# DesignVFD-Ring.net
KiCad netlist of a schematic drawn in EAGLE
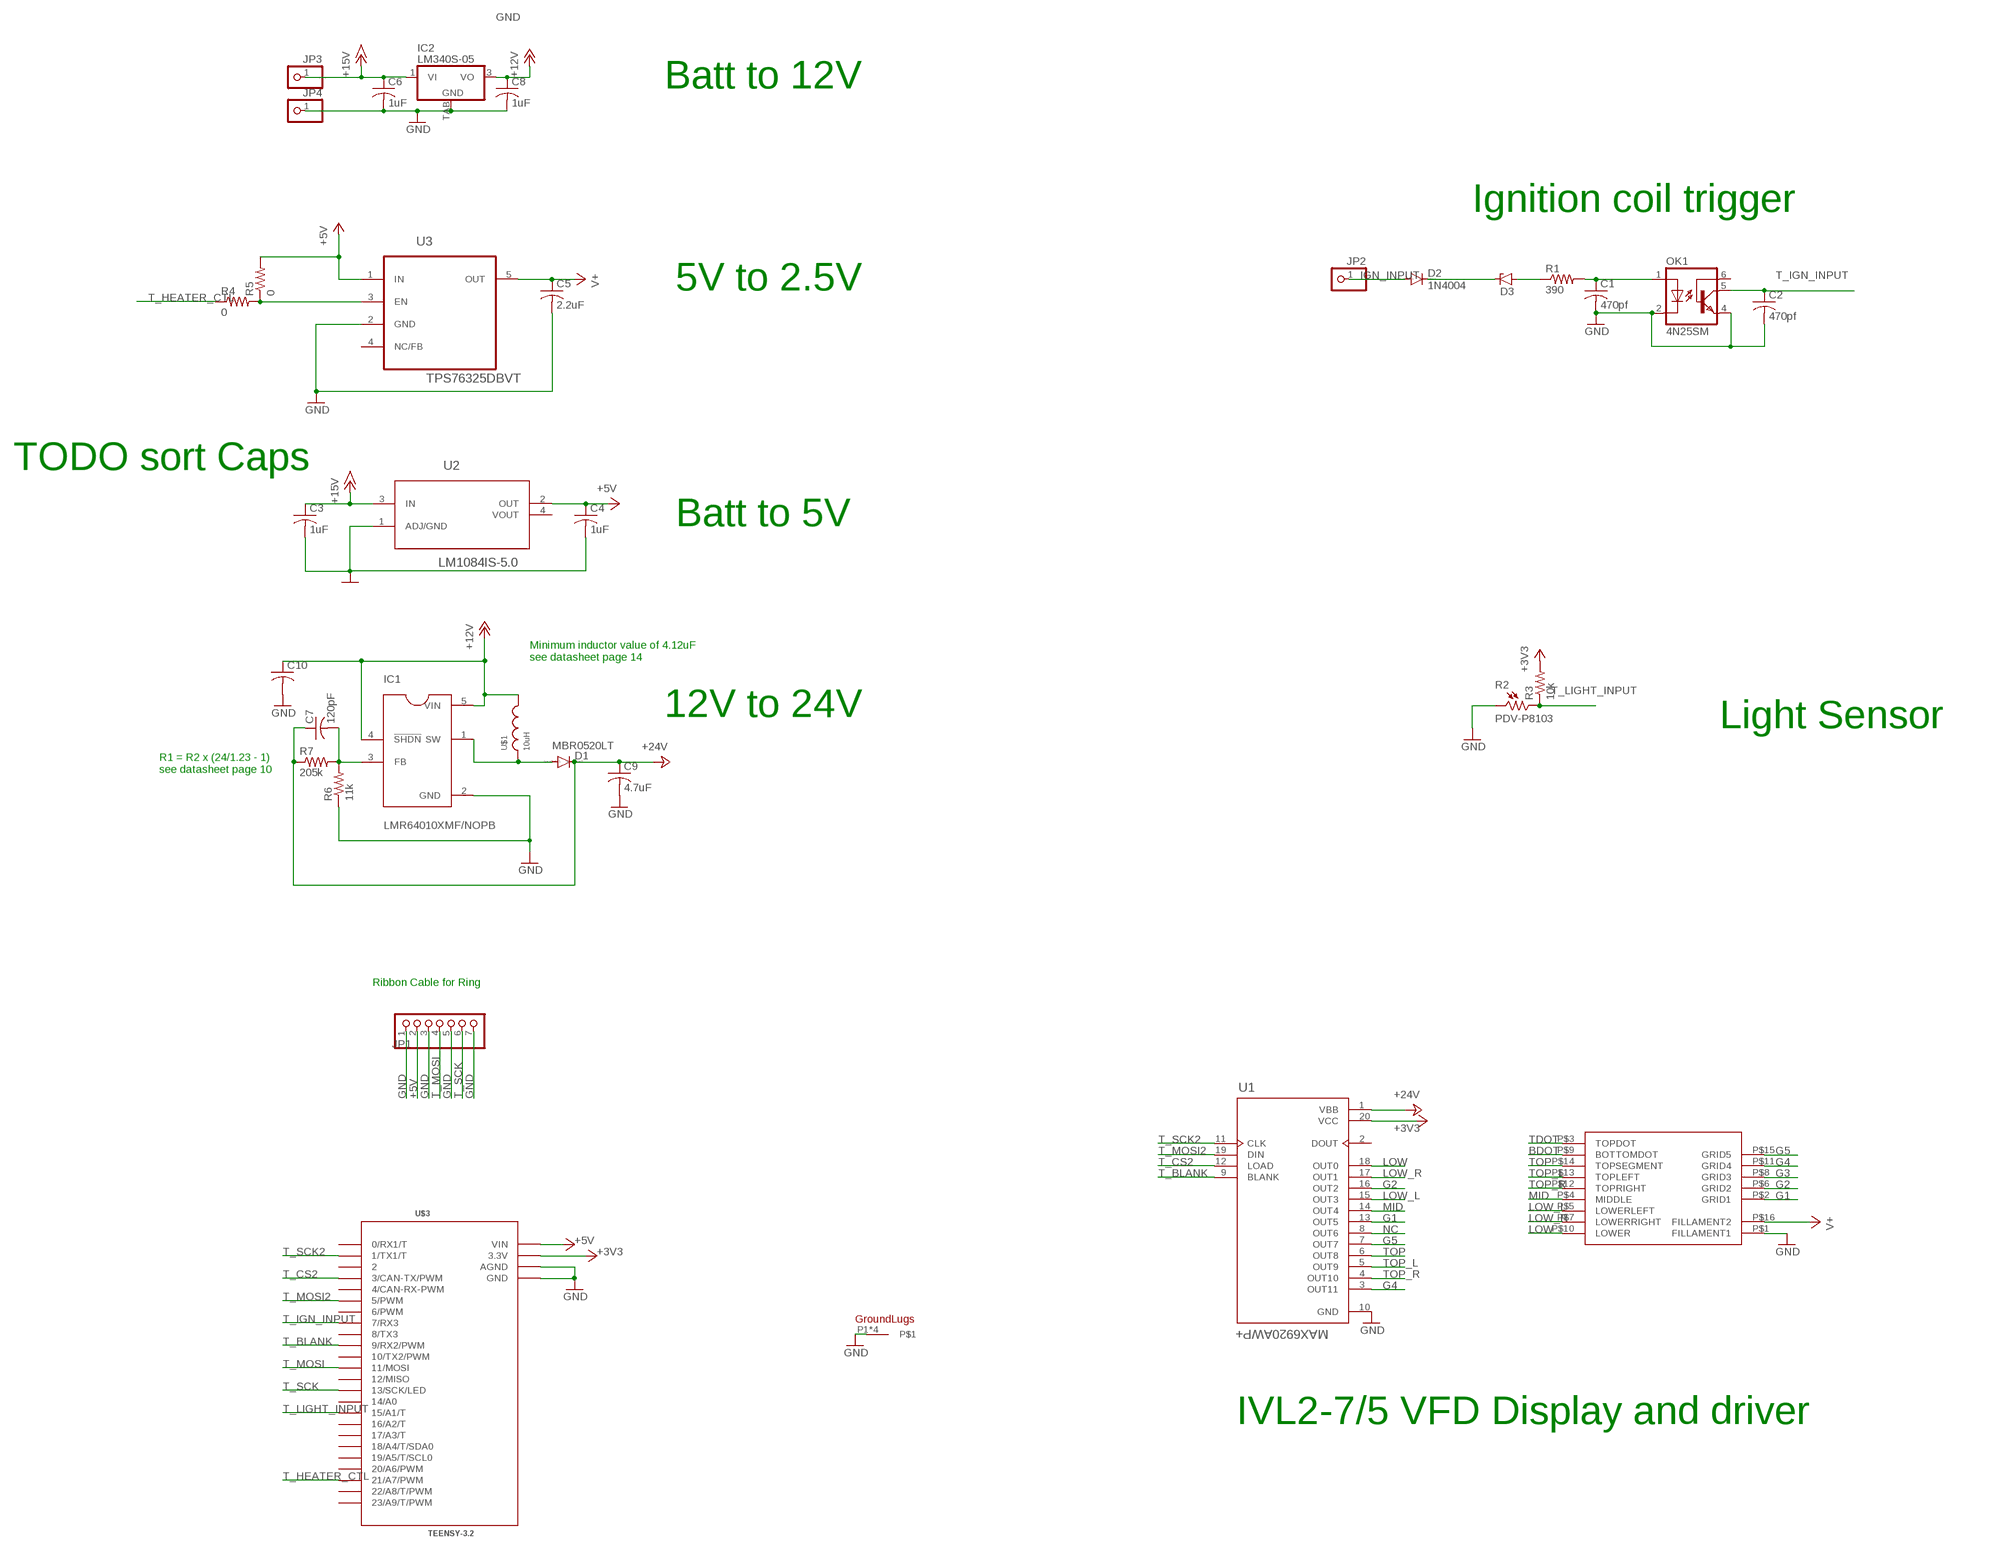
[diagram p0: schematic, sheet 1]

(export (version "E")
  (design (tool "Eeschema 10.0.6"))
  (components
    (comp (ref "C1")
      (value "470pf")
      (footprint "eagle-import:C0805")
      (libsource (lib "eagle-import") (part "C-USC0805"))
    )
    (comp (ref "C2")
      (value "470pf")
      (footprint "eagle-import:C0805")
      (libsource (lib "eagle-import") (part "C-USC0805"))
    )
    (comp (ref "C3")
      (value "1uF")
      (footprint "eagle-import:C0805")
      (libsource (lib "eagle-import") (part "C-USC0805"))
    )
    (comp (ref "C4")
      (value "1uF")
      (footprint "eagle-import:C0805")
      (libsource (lib "eagle-import") (part "C-USC0805"))
    )
    (comp (ref "C5")
      (value "2.2uF")
      (footprint "eagle-import:C0805")
      (libsource (lib "eagle-import") (part "C-USC0805"))
    )
    (comp (ref "C6")
      (value "1uF")
      (footprint "eagle-import:C0805")
      (libsource (lib "eagle-import") (part "C-USC0805"))
    )
    (comp (ref "C7")
      (value "120pF")
      (footprint "eagle-import:C0805")
      (libsource (lib "eagle-import") (part "C-USC0805"))
    )
    (comp (ref "C8")
      (value "1uF")
      (footprint "eagle-import:C0805")
      (libsource (lib "eagle-import") (part "C-USC0805"))
    )
    (comp (ref "C9")
      (value "4.7uF")
      (footprint "eagle-import:C0805")
      (libsource (lib "eagle-import") (part "C-USC0805"))
    )
    (comp (ref "C10")
      (value "C-US025-050X050")
      (footprint "eagle-import:C025-050X050")
      (libsource (lib "eagle-import") (part "C-US025-050X050"))
    )
    (comp (ref "D1")
      (value "MBR0520LT")
      (footprint "eagle-import:SOD123")
      (libsource (lib "eagle-import") (part "MBR0520LT"))
    )
    (comp (ref "D2")
      (value "1N4004")
      (footprint "eagle-import:DO41-10")
      (libsource (lib "eagle-import") (part "1N4004"))
    )
    (comp (ref "D3")
      (value "ZENER-DIODEDO41Z10")
      (footprint "eagle-import:DO41Z10")
      (libsource (lib "eagle-import") (part "ZENER-DIODEDO41Z10"))
    )
    (comp (ref "IC1")
      (value "LMR64010XMF/NOPB")
      (footprint "eagle-import:SOT95P280X145-5N")
      (fields (field (name "DIGI-KEY_PART_NUMBER") "296-38770-1-ND") (field (name "MF") "Texas Instruments"))
      (libsource (lib "eagle-import") (part "LMR64010XMF/NOPB"))
    )
    (comp (ref "IC2")
      (value "LM340S-05")
      (footprint "eagle-import:TO263-3")
      (libsource (lib "eagle-import") (part "LM340?-S05"))
    )
    (comp (ref "JP1")
      (value "PINHD-1X7")
      (footprint "eagle-import:1X07")
      (libsource (lib "eagle-import") (part "PINHD-1X7"))
    )
    (comp (ref "JP2")
      (value "PINHD-1X1")
      (footprint "eagle-import:1X01")
      (libsource (lib "eagle-import") (part "PINHD-1X1"))
    )
    (comp (ref "JP3")
      (value "PINHD-1X1")
      (footprint "eagle-import:1X01")
      (libsource (lib "eagle-import") (part "PINHD-1X1"))
    )
    (comp (ref "JP4")
      (value "PINHD-1X1")
      (footprint "eagle-import:1X01")
      (libsource (lib "eagle-import") (part "PINHD-1X1"))
    )
    (comp (ref "OK1")
      (value "4N25SM")
      (footprint "eagle-import:DIL6-SMD")
      (fields (field (name "MF") "ON Semiconductor"))
      (libsource (lib "eagle-import") (part "4N25SM"))
    )
    (comp (ref "R1")
      (value "390")
      (footprint "eagle-import:R0805")
      (libsource (lib "eagle-import") (part "R-US_R0805"))
    )
    (comp (ref "R2")
      (value "PDV-P8103")
      (footprint "eagle-import:PHODET_PDV-P8103")
      (fields (field (name "MF") "Advanced Photonix"))
      (libsource (lib "eagle-import") (part "PDV-P8103"))
    )
    (comp (ref "R3")
      (value "10k")
      (footprint "eagle-import:R0805")
      (libsource (lib "eagle-import") (part "R-US_R0805"))
    )
    (comp (ref "R4")
      (value "0")
      (footprint "eagle-import:R0805")
      (libsource (lib "eagle-import") (part "R-US_R0805"))
    )
    (comp (ref "R5")
      (value "0")
      (footprint "eagle-import:R0805")
      (libsource (lib "eagle-import") (part "R-US_R0805"))
    )
    (comp (ref "R6")
      (value "11k")
      (footprint "eagle-import:R0805")
      (libsource (lib "eagle-import") (part "R-US_R0805"))
    )
    (comp (ref "R7")
      (value "205k")
      (footprint "eagle-import:R0805")
      (libsource (lib "eagle-import") (part "R-US_R0805"))
    )
    (comp (ref "U$1")
      (value "10uH")
      (footprint "eagle-import:732-1416-ND")
      (libsource (lib "eagle-import") (part "732-1416-ND732-1416-ND"))
    )
    (comp (ref "U$2")
      (value "IVL2-7/5")
      (footprint "eagle-import:IVL2-7_5")
      (libsource (lib "eagle-import") (part "IVL2-7/5"))
    )
    (comp (ref "U$3")
      (value "TEENSY-3.2")
      (footprint "eagle-import:TEENSY3.2")
      (libsource (lib "eagle-import") (part "TEENSY-3.2"))
    )
    (comp (ref "U$4")
      (value "LUMINI3")
      (footprint "eagle-import:STANDOFF-ELECTRICAL")
      (libsource (lib "eagle-import") (part "LUMINI3"))
    )
    (comp (ref "U1")
      (value "MAX6920AWP+")
      (footprint "eagle-import:SOIC127P1032X265-20N")
      (fields (field (name "DIGI-KEY_PART_NUMBER") "MAX6920AWP+-ND") (field (name "MF") "Maxim Integrated"))
      (libsource (lib "eagle-import") (part "MAX6920AWP+"))
    )
    (comp (ref "U2")
      (value "LM1084IS-5.0")
      (footprint "eagle-import:TO254P1435X457-3N")
      (fields (field (name "MF") "Texas Instruments") (field (name "MP") "LM1084IS50"))
      (libsource (lib "eagle-import") (part "LM1084IS-5.0"))
    )
    (comp (ref "U3")
      (value "TPS76325DBVT")
      (footprint "eagle-import:SOT95P280X145-5N")
      (fields (field (name "DIGI-KEY_PART_NUMBER") "296-2701-1-ND") (field (name "MF") "Texas Instruments"))
      (libsource (lib "eagle-import") (part "TPS76325DBVT"))
    )
  )
  (nets
    (net (code "1") (name "+3V3") (class "Default")
      (node (ref "R3") (pin "2") (pinfunction "2_2") (pintype "passive"))
      (node (ref "U$3") (pin "3V3+") (pinfunction "3.3V_3V3+") (pintype "power_in"))
      (node (ref "U1") (pin "20") (pinfunction "VCC_20") (pintype "power_in"))
    )
    (net (code "2") (name "+5V") (class "Default")
      (node (ref "C4") (pin "1") (pinfunction "1_1") (pintype "passive"))
      (node (ref "JP1") (pin "2") (pinfunction "2_2") (pintype "passive"))
      (node (ref "R5") (pin "2") (pinfunction "2_2") (pintype "passive"))
      (node (ref "U$3") (pin "VIN") (pinfunction "VIN_VIN") (pintype "power_in"))
      (node (ref "U2") (pin "2") (pinfunction "OUT_2") (pintype "output"))
      (node (ref "U3") (pin "1") (pinfunction "IN_1") (pintype "power_in"))
    )
    (net (code "3") (name "+12V") (class "Default")
      (node (ref "C10") (pin "1") (pinfunction "1_1") (pintype "passive"))
      (node (ref "C8") (pin "1") (pinfunction "1_1") (pintype "passive"))
      (node (ref "IC1") (pin "4") (pinfunction "~{SHDN}_4") (pintype "input"))
      (node (ref "IC1") (pin "5") (pinfunction "VIN_5") (pintype "power_in"))
      (node (ref "IC2") (pin "3") (pinfunction "VO_3") (pintype "passive"))
      (node (ref "U$1") (pin "P$2") (pinfunction "P$2_P$2") (pintype "bidirectional"))
    )
    (net (code "4") (name "+15V") (class "Default")
      (node (ref "C3") (pin "1") (pinfunction "1_1") (pintype "passive"))
      (node (ref "C6") (pin "1") (pinfunction "1_1") (pintype "passive"))
      (node (ref "IC2") (pin "1") (pinfunction "VI_1") (pintype "input"))
      (node (ref "JP3") (pin "1") (pinfunction "1_1") (pintype "passive"))
      (node (ref "U2") (pin "3") (pinfunction "IN_3") (pintype "power_in"))
    )
    (net (code "5") (name "+24V") (class "Default")
      (node (ref "C7") (pin "1") (pinfunction "1_1") (pintype "passive"))
      (node (ref "C9") (pin "1") (pinfunction "1_1") (pintype "passive"))
      (node (ref "D1") (pin "C") (pinfunction "C_C") (pintype "passive"))
      (node (ref "R7") (pin "1") (pinfunction "1_1") (pintype "passive"))
      (node (ref "U1") (pin "1") (pinfunction "VBB_1") (pintype "power_in"))
    )
    (net (code "6") (name "/BDOT") (class "Default")
      (node (ref "U$2") (pin "P$9") (pinfunction "BOTTOMDOT_P$9") (pintype "bidirectional"))
    )
    (net (code "7") (name "/G1") (class "Default")
      (node (ref "U$2") (pin "P$2") (pinfunction "GRID1_P$2") (pintype "bidirectional"))
      (node (ref "U1") (pin "13") (pinfunction "OUT5_13") (pintype "output"))
    )
    (net (code "8") (name "/G2") (class "Default")
      (node (ref "U$2") (pin "P$6") (pinfunction "GRID2_P$6") (pintype "bidirectional"))
      (node (ref "U1") (pin "16") (pinfunction "OUT2_16") (pintype "output"))
    )
    (net (code "9") (name "/G3") (class "Default")
      (node (ref "U$2") (pin "P$8") (pinfunction "GRID3_P$8") (pintype "bidirectional"))
    )
    (net (code "10") (name "/G4") (class "Default")
      (node (ref "U$2") (pin "P$11") (pinfunction "GRID4_P$11") (pintype "bidirectional"))
      (node (ref "U1") (pin "3") (pinfunction "OUT11_3") (pintype "output"))
    )
    (net (code "11") (name "/G5") (class "Default")
      (node (ref "U$2") (pin "P$15") (pinfunction "GRID5_P$15") (pintype "bidirectional"))
      (node (ref "U1") (pin "7") (pinfunction "OUT7_7") (pintype "output"))
    )
    (net (code "12") (name "/IGN_INPUT") (class "Default")
      (node (ref "D2") (pin "A") (pinfunction "A_A") (pintype "passive"))
      (node (ref "JP2") (pin "1") (pinfunction "1_1") (pintype "passive"))
    )
    (net (code "13") (name "/LOW") (class "Default")
      (node (ref "U$2") (pin "P$10") (pinfunction "LOWER_P$10") (pintype "bidirectional"))
      (node (ref "U1") (pin "18") (pinfunction "OUT0_18") (pintype "output"))
    )
    (net (code "14") (name "/LOW_L") (class "Default")
      (node (ref "U$2") (pin "P$5") (pinfunction "LOWERLEFT_P$5") (pintype "bidirectional"))
      (node (ref "U1") (pin "15") (pinfunction "OUT3_15") (pintype "output"))
    )
    (net (code "15") (name "/LOW_R") (class "Default")
      (node (ref "U$2") (pin "P$7") (pinfunction "LOWERRIGHT_P$7") (pintype "bidirectional"))
      (node (ref "U1") (pin "17") (pinfunction "OUT1_17") (pintype "output"))
    )
    (net (code "16") (name "/MID") (class "Default")
      (node (ref "U$2") (pin "P$4") (pinfunction "MIDDLE_P$4") (pintype "bidirectional"))
      (node (ref "U1") (pin "14") (pinfunction "OUT4_14") (pintype "output"))
    )
    (net (code "17") (name "/NC") (class "Default")
      (node (ref "U1") (pin "8") (pinfunction "OUT6_8") (pintype "output"))
    )
    (net (code "18") (name "/TDOT") (class "Default")
      (node (ref "U$2") (pin "P$3") (pinfunction "TOPDOT_P$3") (pintype "bidirectional"))
    )
    (net (code "19") (name "/TOP") (class "Default")
      (node (ref "U$2") (pin "P$14") (pinfunction "TOPSEGMENT_P$14") (pintype "bidirectional"))
      (node (ref "U1") (pin "6") (pinfunction "OUT8_6") (pintype "output"))
    )
    (net (code "20") (name "/TOP_L") (class "Default")
      (node (ref "U$2") (pin "P$13") (pinfunction "TOPLEFT_P$13") (pintype "bidirectional"))
      (node (ref "U1") (pin "5") (pinfunction "OUT9_5") (pintype "output"))
    )
    (net (code "21") (name "/TOP_R") (class "Default")
      (node (ref "U$2") (pin "P$12") (pinfunction "TOPRIGHT_P$12") (pintype "bidirectional"))
      (node (ref "U1") (pin "4") (pinfunction "OUT10_4") (pintype "output"))
    )
    (net (code "22") (name "/T_BLANK") (class "Default")
      (node (ref "U$3") (pin "9") (pinfunction "9/RX2/PWM_9") (pintype "bidirectional"))
      (node (ref "U1") (pin "9") (pinfunction "BLANK_9") (pintype "input"))
    )
    (net (code "23") (name "/T_CS2") (class "Default")
      (node (ref "U$3") (pin "3") (pinfunction "3/CAN-TX/PWM_3") (pintype "bidirectional"))
      (node (ref "U1") (pin "12") (pinfunction "LOAD_12") (pintype "input"))
    )
    (net (code "24") (name "/T_HEATER_CTL") (class "Default")
      (node (ref "R4") (pin "1") (pinfunction "1_1") (pintype "passive"))
      (node (ref "U$3") (pin "21") (pinfunction "21/A7/PWM_21") (pintype "bidirectional"))
    )
    (net (code "25") (name "/T_IGN_INPUT") (class "Default")
      (node (ref "C2") (pin "1") (pinfunction "1_1") (pintype "passive"))
      (node (ref "OK1") (pin "5") (pinfunction "COL_5") (pintype "passive"))
      (node (ref "U$3") (pin "7") (pinfunction "7/RX3_7") (pintype "bidirectional"))
    )
    (net (code "26") (name "/T_LIGHT_INPUT") (class "Default")
      (node (ref "R2") (pin "2") (pinfunction "2_2") (pintype "passive"))
      (node (ref "R3") (pin "1") (pinfunction "1_1") (pintype "passive"))
      (node (ref "U$3") (pin "15") (pinfunction "15/A1/T_15") (pintype "bidirectional"))
    )
    (net (code "27") (name "/T_MOSI") (class "Default")
      (node (ref "JP1") (pin "4") (pinfunction "4_4") (pintype "passive"))
      (node (ref "U$3") (pin "11") (pinfunction "11/MOSI_11") (pintype "bidirectional"))
    )
    (net (code "28") (name "/T_MOSI2") (class "Default")
      (node (ref "U$3") (pin "5") (pinfunction "5/PWM_5") (pintype "bidirectional"))
      (node (ref "U1") (pin "19") (pinfunction "DIN_19") (pintype "input"))
    )
    (net (code "29") (name "/T_SCK") (class "Default")
      (node (ref "JP1") (pin "6") (pinfunction "6_6") (pintype "passive"))
      (node (ref "U$3") (pin "13") (pinfunction "13/SCK/LED_13") (pintype "bidirectional"))
    )
    (net (code "30") (name "/T_SCK2") (class "Default")
      (node (ref "U$3") (pin "1") (pinfunction "1/TX1/T_1") (pintype "bidirectional"))
      (node (ref "U1") (pin "11") (pinfunction "CLK_11") (pintype "input"))
    )
    (net (code "31") (name "GND") (class "Default")
      (node (ref "C1") (pin "2") (pinfunction "2_2") (pintype "passive"))
      (node (ref "C10") (pin "2") (pinfunction "2_2") (pintype "passive"))
      (node (ref "C2") (pin "2") (pinfunction "2_2") (pintype "passive"))
      (node (ref "C3") (pin "2") (pinfunction "2_2") (pintype "passive"))
      (node (ref "C4") (pin "2") (pinfunction "2_2") (pintype "passive"))
      (node (ref "C5") (pin "2") (pinfunction "2_2") (pintype "passive"))
      (node (ref "C6") (pin "2") (pinfunction "2_2") (pintype "passive"))
      (node (ref "C8") (pin "2") (pinfunction "2_2") (pintype "passive"))
      (node (ref "C9") (pin "2") (pinfunction "2_2") (pintype "passive"))
      (node (ref "IC1") (pin "2") (pinfunction "GND_2") (pintype "passive"))
      (node (ref "IC2") (pin "TAB") (pinfunction "GND_TAB") (pintype "passive"))
      (node (ref "JP1") (pin "1") (pinfunction "1_1") (pintype "passive"))
      (node (ref "JP1") (pin "3") (pinfunction "3_3") (pintype "passive"))
      (node (ref "JP1") (pin "5") (pinfunction "5_5") (pintype "passive"))
      (node (ref "JP1") (pin "7") (pinfunction "7_7") (pintype "passive"))
      (node (ref "JP4") (pin "1") (pinfunction "1_1") (pintype "passive"))
      (node (ref "OK1") (pin "2") (pinfunction "C_2") (pintype "passive"))
      (node (ref "OK1") (pin "4") (pinfunction "EMI_4") (pintype "passive"))
      (node (ref "R2") (pin "1") (pinfunction "1_1") (pintype "passive"))
      (node (ref "R6") (pin "1") (pinfunction "1_1") (pintype "passive"))
      (node (ref "U$2") (pin "P$1") (pinfunction "FILLAMENT1_P$1") (pintype "bidirectional"))
      (node (ref "U$3") (pin "AGND") (pinfunction "AGND_AGND") (pintype "power_in"))
      (node (ref "U$3") (pin "GND") (pinfunction "GND_GND") (pintype "power_in"))
      (node (ref "U$4") (pin "P1") (pinfunction "P$1_P1") (pintype "bidirectional"))
      (node (ref "U$4") (pin "P2") (pinfunction "P$1_P2") (pintype "bidirectional"))
      (node (ref "U$4") (pin "P3") (pinfunction "P$1_P3") (pintype "bidirectional"))
      (node (ref "U$4") (pin "P4") (pinfunction "P$1_P4") (pintype "bidirectional"))
      (node (ref "U1") (pin "10") (pinfunction "GND_10") (pintype "power_in"))
      (node (ref "U2") (pin "1") (pinfunction "ADJ/GND_1") (pintype "passive"))
      (node (ref "U3") (pin "2") (pinfunction "GND_2") (pintype "passive"))
    )
    (net (code "32") (name "Net-(D2-PadC)") (class "Default")
      (node (ref "D2") (pin "C") (pinfunction "C_C") (pintype "passive"))
      (node (ref "D3") (pin "C") (pinfunction "C_C") (pintype "passive"))
    )
    (net (code "33") (name "Net-(D3-PadA)") (class "Default")
      (node (ref "D3") (pin "A") (pinfunction "A_A") (pintype "passive"))
      (node (ref "R1") (pin "1") (pinfunction "1_1") (pintype "passive"))
    )
    (net (code "34") (name "Net-(IC1-FB)") (class "Default")
      (node (ref "C7") (pin "2") (pinfunction "2_2") (pintype "passive"))
      (node (ref "IC1") (pin "3") (pinfunction "FB_3") (pintype "passive"))
      (node (ref "R6") (pin "2") (pinfunction "2_2") (pintype "passive"))
      (node (ref "R7") (pin "2") (pinfunction "2_2") (pintype "passive"))
    )
    (net (code "35") (name "Net-(IC1-SW)") (class "Default")
      (node (ref "D1") (pin "A") (pinfunction "A_A") (pintype "passive"))
      (node (ref "IC1") (pin "1") (pinfunction "SW_1") (pintype "output"))
      (node (ref "U$1") (pin "P$1") (pinfunction "P$1_P$1") (pintype "bidirectional"))
    )
    (net (code "36") (name "Net-(OK1-A)") (class "Default")
      (node (ref "C1") (pin "1") (pinfunction "1_1") (pintype "passive"))
      (node (ref "OK1") (pin "1") (pinfunction "A_1") (pintype "passive"))
      (node (ref "R1") (pin "2") (pinfunction "2_2") (pintype "passive"))
    )
    (net (code "37") (name "Net-(U3-EN)") (class "Default")
      (node (ref "R4") (pin "2") (pinfunction "2_2") (pintype "passive"))
      (node (ref "R5") (pin "1") (pinfunction "1_1") (pintype "passive"))
      (node (ref "U3") (pin "3") (pinfunction "EN_3") (pintype "input"))
    )
    (net (code "38") (name "V+") (class "Default")
      (node (ref "C5") (pin "1") (pinfunction "1_1") (pintype "passive"))
      (node (ref "U$2") (pin "P$16") (pinfunction "FILLAMENT2_P$16") (pintype "bidirectional"))
      (node (ref "U3") (pin "5") (pinfunction "OUT_5") (pintype "output"))
    )
    (net (code "39") (name "unconnected-(OK1-BAS-Pad6)") (class "Default")
      (node (ref "OK1") (pin "6") (pinfunction "BAS_6") (pintype "passive"))
    )
    (net (code "40") (name "unconnected-(U$3-0{slash}RX1{slash}T-Pad0)") (class "Default")
      (node (ref "U$3") (pin "0") (pinfunction "0/RX1/T_0") (pintype "bidirectional"))
    )
    (net (code "41") (name "unconnected-(U$3-4{slash}CAN-RX-PWM-Pad4)") (class "Default")
      (node (ref "U$3") (pin "4") (pinfunction "4/CAN-RX-PWM_4") (pintype "bidirectional"))
    )
    (net (code "42") (name "unconnected-(U$3-6{slash}PWM-Pad6)") (class "Default")
      (node (ref "U$3") (pin "6") (pinfunction "6/PWM_6") (pintype "bidirectional"))
    )
    (net (code "43") (name "unconnected-(U$3-8{slash}TX3-Pad8)") (class "Default")
      (node (ref "U$3") (pin "8") (pinfunction "8/TX3_8") (pintype "bidirectional"))
    )
    (net (code "44") (name "unconnected-(U$3-10{slash}TX2{slash}PWM-Pad10)") (class "Default")
      (node (ref "U$3") (pin "10") (pinfunction "10/TX2/PWM_10") (pintype "bidirectional"))
    )
    (net (code "45") (name "unconnected-(U$3-12{slash}MISO-Pad12)") (class "Default")
      (node (ref "U$3") (pin "12") (pinfunction "12/MISO_12") (pintype "bidirectional"))
    )
    (net (code "46") (name "unconnected-(U$3-14{slash}A0-Pad14)") (class "Default")
      (node (ref "U$3") (pin "14") (pinfunction "14/A0_14") (pintype "bidirectional"))
    )
    (net (code "47") (name "unconnected-(U$3-16{slash}A2{slash}T-Pad16)") (class "Default")
      (node (ref "U$3") (pin "16") (pinfunction "16/A2/T_16") (pintype "bidirectional"))
    )
    (net (code "48") (name "unconnected-(U$3-17{slash}A3{slash}T-Pad17)") (class "Default")
      (node (ref "U$3") (pin "17") (pinfunction "17/A3/T_17") (pintype "bidirectional"))
    )
    (net (code "49") (name "unconnected-(U$3-18{slash}A4{slash}T{slash}SDA0-Pad18)") (class "Default")
      (node (ref "U$3") (pin "18") (pinfunction "18/A4/T/SDA0_18") (pintype "bidirectional"))
    )
    (net (code "50") (name "unconnected-(U$3-19{slash}A5{slash}T{slash}SCL0-Pad19)") (class "Default")
      (node (ref "U$3") (pin "19") (pinfunction "19/A5/T/SCL0_19") (pintype "bidirectional"))
    )
    (net (code "51") (name "unconnected-(U$3-20{slash}A6{slash}PWM-Pad20)") (class "Default")
      (node (ref "U$3") (pin "20") (pinfunction "20/A6/PWM_20") (pintype "bidirectional"))
    )
    (net (code "52") (name "unconnected-(U$3-22{slash}A8{slash}T{slash}PWM-Pad22)") (class "Default")
      (node (ref "U$3") (pin "22") (pinfunction "22/A8/T/PWM_22") (pintype "bidirectional"))
    )
    (net (code "53") (name "unconnected-(U$3-23{slash}A9{slash}T{slash}PWM-Pad23)") (class "Default")
      (node (ref "U$3") (pin "23") (pinfunction "23/A9/T/PWM_23") (pintype "bidirectional"))
    )
    (net (code "54") (name "unconnected-(U$3-Pad2)") (class "Default")
      (node (ref "U$3") (pin "2") (pinfunction "2_2") (pintype "bidirectional"))
    )
    (net (code "55") (name "unconnected-(U1-DOUT-Pad2)") (class "Default")
      (node (ref "U1") (pin "2") (pinfunction "DOUT_2") (pintype "output"))
    )
    (net (code "56") (name "unconnected-(U2-VOUT-Pad4)") (class "Default")
      (node (ref "U2") (pin "4") (pinfunction "VOUT_4") (pintype "output"))
    )
    (net (code "57") (name "unconnected-(U3-NC{slash}FB-Pad4)") (class "Default")
      (node (ref "U3") (pin "4") (pinfunction "NC/FB_4") (pintype "no_connect"))
    )
  )
)
